# alt1_2.net
KiCad netlist of a schematic drawn in EAGLE
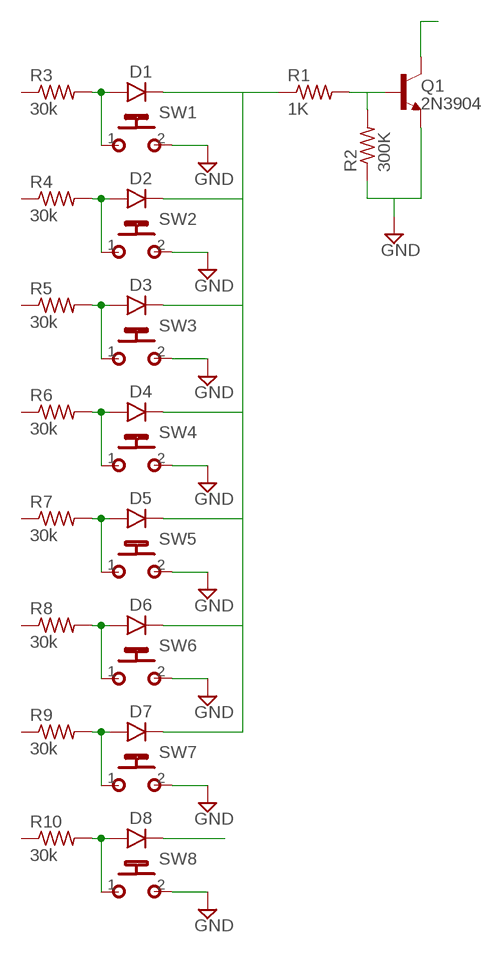
[diagram p0: schematic, sheet 1]

(export (version "E")
  (design (tool "Eeschema 10.0.6"))
  (components
    (comp (ref "D1")
      (value "1N4148-3")
      (footprint "eagle-import:DO35-3")
      (libsource (lib "eagle-import") (part "1N4148-3"))
    )
    (comp (ref "D2")
      (value "1N4148-3")
      (footprint "eagle-import:DO35-3")
      (libsource (lib "eagle-import") (part "1N4148-3"))
    )
    (comp (ref "D3")
      (value "1N4148-3")
      (footprint "eagle-import:DO35-3")
      (libsource (lib "eagle-import") (part "1N4148-3"))
    )
    (comp (ref "D4")
      (value "1N4148-3")
      (footprint "eagle-import:DO35-3")
      (libsource (lib "eagle-import") (part "1N4148-3"))
    )
    (comp (ref "D5")
      (value "1N4148-3")
      (footprint "eagle-import:DO35-3")
      (libsource (lib "eagle-import") (part "1N4148-3"))
    )
    (comp (ref "D6")
      (value "1N4148-3")
      (footprint "eagle-import:DO35-3")
      (libsource (lib "eagle-import") (part "1N4148-3"))
    )
    (comp (ref "D7")
      (value "1N4148-3")
      (footprint "eagle-import:DO35-3")
      (libsource (lib "eagle-import") (part "1N4148-3"))
    )
    (comp (ref "D8")
      (value "1N4148-3")
      (footprint "eagle-import:DO35-3")
      (libsource (lib "eagle-import") (part "1N4148-3"))
    )
    (comp (ref "Q1")
      (value "2N3904")
      (footprint "eagle-import:TO92-")
      (libsource (lib "eagle-import") (part "2N3904"))
    )
    (comp (ref "R1")
      (value "1K")
      (footprint "eagle-import:R0207_3")
      (libsource (lib "eagle-import") (part "6MM.3"))
    )
    (comp (ref "R2")
      (value "300K")
      (footprint "eagle-import:R0207_3")
      (libsource (lib "eagle-import") (part "6MM.3"))
    )
    (comp (ref "R3")
      (value "30k")
      (footprint "eagle-import:R0207_3")
      (libsource (lib "eagle-import") (part "6MM.3"))
    )
    (comp (ref "R4")
      (value "30k")
      (footprint "eagle-import:R0207_3")
      (libsource (lib "eagle-import") (part "6MM.3"))
    )
    (comp (ref "R5")
      (value "30k")
      (footprint "eagle-import:R0207_3")
      (libsource (lib "eagle-import") (part "6MM.3"))
    )
    (comp (ref "R6")
      (value "30k")
      (footprint "eagle-import:R0207_3")
      (libsource (lib "eagle-import") (part "6MM.3"))
    )
    (comp (ref "R7")
      (value "30k")
      (footprint "eagle-import:R0207_3")
      (libsource (lib "eagle-import") (part "6MM.3"))
    )
    (comp (ref "R8")
      (value "30k")
      (footprint "eagle-import:R0207_3")
      (libsource (lib "eagle-import") (part "6MM.3"))
    )
    (comp (ref "R9")
      (value "30k")
      (footprint "eagle-import:R0207_3")
      (libsource (lib "eagle-import") (part "6MM.3"))
    )
    (comp (ref "R10")
      (value "30k")
      (footprint "eagle-import:R0207_3")
      (libsource (lib "eagle-import") (part "6MM.3"))
    )
    (comp (ref "SW1")
      (value "MOMENTARYSPST1")
      (footprint "eagle-import:SPST")
      (libsource (lib "eagle-import") (part "MOMENTARYSPST1"))
    )
    (comp (ref "SW2")
      (value "MOMENTARYSPST1")
      (footprint "eagle-import:SPST")
      (libsource (lib "eagle-import") (part "MOMENTARYSPST1"))
    )
    (comp (ref "SW3")
      (value "MOMENTARYSPST1")
      (footprint "eagle-import:SPST")
      (libsource (lib "eagle-import") (part "MOMENTARYSPST1"))
    )
    (comp (ref "SW4")
      (value "MOMENTARYSPST1")
      (footprint "eagle-import:SPST")
      (libsource (lib "eagle-import") (part "MOMENTARYSPST1"))
    )
    (comp (ref "SW5")
      (value "MOMENTARYSPST1")
      (footprint "eagle-import:SPST")
      (libsource (lib "eagle-import") (part "MOMENTARYSPST1"))
    )
    (comp (ref "SW6")
      (value "MOMENTARYSPST1")
      (footprint "eagle-import:SPST")
      (libsource (lib "eagle-import") (part "MOMENTARYSPST1"))
    )
    (comp (ref "SW7")
      (value "MOMENTARYSPST1")
      (footprint "eagle-import:SPST")
      (libsource (lib "eagle-import") (part "MOMENTARYSPST1"))
    )
    (comp (ref "SW8")
      (value "MOMENTARYSPST1")
      (footprint "eagle-import:SPST")
      (libsource (lib "eagle-import") (part "MOMENTARYSPST1"))
    )
  )
  (nets
    (net (code "1") (name "GND") (class "Default")
      (node (ref "Q1") (pin "3") (pinfunction "E_3") (pintype "passive"))
      (node (ref "R2") (pin "1") (pinfunction "1_1") (pintype "passive"))
      (node (ref "SW1") (pin "2") (pinfunction "S_2") (pintype "passive"))
      (node (ref "SW2") (pin "2") (pinfunction "S_2") (pintype "passive"))
      (node (ref "SW3") (pin "2") (pinfunction "S_2") (pintype "passive"))
      (node (ref "SW4") (pin "2") (pinfunction "S_2") (pintype "passive"))
      (node (ref "SW5") (pin "2") (pinfunction "S_2") (pintype "passive"))
      (node (ref "SW6") (pin "2") (pinfunction "S_2") (pintype "passive"))
      (node (ref "SW7") (pin "2") (pinfunction "S_2") (pintype "passive"))
      (node (ref "SW8") (pin "2") (pinfunction "S_2") (pintype "passive"))
    )
    (net (code "2") (name "Net-(D1-PadC)") (class "Default")
      (node (ref "D1") (pin "C") (pinfunction "C_C") (pintype "passive"))
      (node (ref "D2") (pin "C") (pinfunction "C_C") (pintype "passive"))
      (node (ref "D3") (pin "C") (pinfunction "C_C") (pintype "passive"))
      (node (ref "D4") (pin "C") (pinfunction "C_C") (pintype "passive"))
      (node (ref "D5") (pin "C") (pinfunction "C_C") (pintype "passive"))
      (node (ref "D6") (pin "C") (pinfunction "C_C") (pintype "passive"))
      (node (ref "D7") (pin "C") (pinfunction "C_C") (pintype "passive"))
      (node (ref "R1") (pin "1") (pinfunction "1_1") (pintype "passive"))
    )
    (net (code "3") (name "Net-(Q1-B)") (class "Default")
      (node (ref "Q1") (pin "2") (pinfunction "B_2") (pintype "passive"))
      (node (ref "R1") (pin "2") (pinfunction "2_2") (pintype "passive"))
      (node (ref "R2") (pin "2") (pinfunction "2_2") (pintype "passive"))
    )
    (net (code "4") (name "Net-(SW1-P)") (class "Default")
      (node (ref "D1") (pin "A") (pinfunction "A_A") (pintype "passive"))
      (node (ref "R3") (pin "2") (pinfunction "2_2") (pintype "passive"))
      (node (ref "SW1") (pin "1") (pinfunction "P_1") (pintype "passive"))
    )
    (net (code "5") (name "Net-(SW2-P)") (class "Default")
      (node (ref "D2") (pin "A") (pinfunction "A_A") (pintype "passive"))
      (node (ref "R4") (pin "2") (pinfunction "2_2") (pintype "passive"))
      (node (ref "SW2") (pin "1") (pinfunction "P_1") (pintype "passive"))
    )
    (net (code "6") (name "Net-(SW3-P)") (class "Default")
      (node (ref "D3") (pin "A") (pinfunction "A_A") (pintype "passive"))
      (node (ref "R5") (pin "2") (pinfunction "2_2") (pintype "passive"))
      (node (ref "SW3") (pin "1") (pinfunction "P_1") (pintype "passive"))
    )
    (net (code "7") (name "Net-(SW4-P)") (class "Default")
      (node (ref "D4") (pin "A") (pinfunction "A_A") (pintype "passive"))
      (node (ref "R6") (pin "2") (pinfunction "2_2") (pintype "passive"))
      (node (ref "SW4") (pin "1") (pinfunction "P_1") (pintype "passive"))
    )
    (net (code "8") (name "Net-(SW5-P)") (class "Default")
      (node (ref "D5") (pin "A") (pinfunction "A_A") (pintype "passive"))
      (node (ref "R7") (pin "2") (pinfunction "2_2") (pintype "passive"))
      (node (ref "SW5") (pin "1") (pinfunction "P_1") (pintype "passive"))
    )
    (net (code "9") (name "Net-(SW6-P)") (class "Default")
      (node (ref "D6") (pin "A") (pinfunction "A_A") (pintype "passive"))
      (node (ref "R8") (pin "2") (pinfunction "2_2") (pintype "passive"))
      (node (ref "SW6") (pin "1") (pinfunction "P_1") (pintype "passive"))
    )
    (net (code "10") (name "Net-(SW7-P)") (class "Default")
      (node (ref "D7") (pin "A") (pinfunction "A_A") (pintype "passive"))
      (node (ref "R9") (pin "2") (pinfunction "2_2") (pintype "passive"))
      (node (ref "SW7") (pin "1") (pinfunction "P_1") (pintype "passive"))
    )
    (net (code "11") (name "Net-(SW8-P)") (class "Default")
      (node (ref "D8") (pin "A") (pinfunction "A_A") (pintype "passive"))
      (node (ref "R10") (pin "2") (pinfunction "2_2") (pintype "passive"))
      (node (ref "SW8") (pin "1") (pinfunction "P_1") (pintype "passive"))
    )
    (net (code "12") (name "unconnected-(D8-PadC)") (class "Default")
      (node (ref "D8") (pin "C") (pinfunction "C_C") (pintype "passive"))
    )
    (net (code "13") (name "unconnected-(Q1-C-Pad1)") (class "Default")
      (node (ref "Q1") (pin "1") (pinfunction "C_1") (pintype "passive"))
    )
    (net (code "14") (name "unconnected-(R3-Pad1)") (class "Default")
      (node (ref "R3") (pin "1") (pinfunction "1_1") (pintype "passive"))
    )
    (net (code "15") (name "unconnected-(R4-Pad1)") (class "Default")
      (node (ref "R4") (pin "1") (pinfunction "1_1") (pintype "passive"))
    )
    (net (code "16") (name "unconnected-(R5-Pad1)") (class "Default")
      (node (ref "R5") (pin "1") (pinfunction "1_1") (pintype "passive"))
    )
    (net (code "17") (name "unconnected-(R6-Pad1)") (class "Default")
      (node (ref "R6") (pin "1") (pinfunction "1_1") (pintype "passive"))
    )
    (net (code "18") (name "unconnected-(R7-Pad1)") (class "Default")
      (node (ref "R7") (pin "1") (pinfunction "1_1") (pintype "passive"))
    )
    (net (code "19") (name "unconnected-(R8-Pad1)") (class "Default")
      (node (ref "R8") (pin "1") (pinfunction "1_1") (pintype "passive"))
    )
    (net (code "20") (name "unconnected-(R9-Pad1)") (class "Default")
      (node (ref "R9") (pin "1") (pinfunction "1_1") (pintype "passive"))
    )
    (net (code "21") (name "unconnected-(R10-Pad1)") (class "Default")
      (node (ref "R10") (pin "1") (pinfunction "1_1") (pintype "passive"))
    )
  )
)
